# Arduino_connectors.net
KiCad netlist of a schematic drawn in Altium Designer
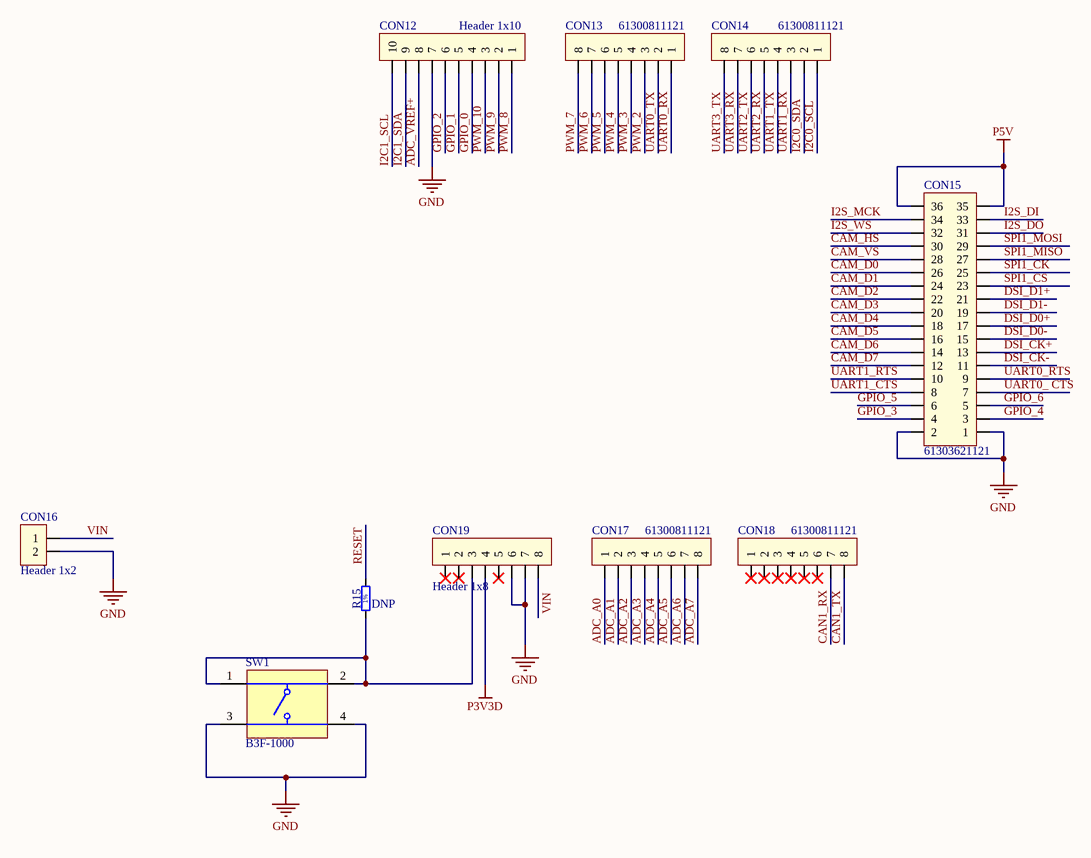
[diagram p0: Arduino connectors.SchDoc]

(export (version "E")
  (design (tool "Eeschema 10.0.6"))
  (components
    (comp (ref "CON12")
      (value "Header 1x10")
      (footprint "61301011121")
      (libsource (lib "MIRION Technologies (CANBERRA Olen) NV") (part "CON10"))
    )
    (comp (ref "CON13")
      (value "61300811121")
      (footprint "61300811121")
      (description "Board-To-Board Connector, Vertical, Wr-Phd Series, Through Hole, Header, 8, 2.54 Mm")
      (libsource (lib "MIRION Technologies (CANBERRA Olen) NV") (part "CON8"))
    )
    (comp (ref "CON14")
      (value "61300811121")
      (footprint "61300811121")
      (description "Board-To-Board Connector, Vertical, Wr-Phd Series, Through Hole, Header, 8, 2.54 Mm")
      (libsource (lib "MIRION Technologies (CANBERRA Olen) NV") (part "CON8"))
    )
    (comp (ref "CON15")
      (value "61303621121")
      (footprint "61303621121")
      (libsource (lib "MIRION Technologies (CANBERRA Olen) NV") (part "CON36"))
    )
    (comp (ref "CON16")
      (value "Header 1x2")
      (footprint "61300211121")
      (description "Header 1x2 2.54mm")
      (libsource (lib "MIRION Technologies (CANBERRA Olen) NV") (part "CON2"))
    )
    (comp (ref "CON17")
      (value "61300811121")
      (footprint "61300811121")
      (description "Board-To-Board Connector, Vertical, Wr-Phd Series, Through Hole, Header, 8, 2.54 Mm")
      (libsource (lib "") (part "CON8_1"))
    )
    (comp (ref "CON18")
      (value "61300811121")
      (footprint "61300811121")
      (description "Board-To-Board Connector, Vertical, Wr-Phd Series, Through Hole, Header, 8, 2.54 Mm")
      (libsource (lib "") (part "CON8_1"))
    )
    (comp (ref "CON19") (value "Header 1x8") (footprint "61300811121") (libsource (lib "") (part "CON8_1")))
    (comp (ref "R15")
      (value "DNP")
      (footprint "R0603")
      (description "generic 0603 Thick film resistor")
      (fields (field (name "VOLTAGE") "75V") (field (name "POWER") "100mW"))
      (libsource (lib "MIRION Technologies (CANBERRA Olen) NV") (part "res_1pct"))
    )
    (comp (ref "SW1")
      (value "B3F-1000")
      (footprint "OMRON-B3F-1000-4_V")
      (description "Tactile Switch, SPST-NO, 0.05 A, 24 V, -25 to 70 degC, 4-Pin THD, RoHS, Bulk")
      (fields (field (name "MANUFACTURER") "Omron Electronic Components"))
      (libsource (lib "MIRION Technologies (CANBERRA Olen) NV") (part "SW-SPST-4_A"))
    )
  )
  (nets
    (net (code "1") (name "/ADC_A0") (class "Default")
      (node (ref "CON17") (pin "1") (pinfunction "1_1") (pintype "passive"))
    )
    (net (code "2") (name "/ADC_A1") (class "Default")
      (node (ref "CON17") (pin "2") (pinfunction "2_2") (pintype "passive"))
    )
    (net (code "3") (name "/ADC_A2") (class "Default")
      (node (ref "CON17") (pin "3") (pinfunction "3_3") (pintype "passive"))
    )
    (net (code "4") (name "/ADC_A3") (class "Default")
      (node (ref "CON17") (pin "4") (pinfunction "4_4") (pintype "passive"))
    )
    (net (code "5") (name "/ADC_A4") (class "Default")
      (node (ref "CON17") (pin "5") (pinfunction "5_5") (pintype "passive"))
    )
    (net (code "6") (name "/ADC_A5") (class "Default")
      (node (ref "CON17") (pin "6") (pinfunction "6_6") (pintype "passive"))
    )
    (net (code "7") (name "/ADC_A6") (class "Default")
      (node (ref "CON17") (pin "7") (pinfunction "7_7") (pintype "passive"))
    )
    (net (code "8") (name "/ADC_A7") (class "Default")
      (node (ref "CON17") (pin "8") (pinfunction "8_8") (pintype "passive"))
    )
    (net (code "9") (name "/ADC_VREF+") (class "Default")
      (node (ref "CON12") (pin "8") (pinfunction "8_8") (pintype "passive"))
    )
    (net (code "10") (name "/CAM_D0") (class "Default")
      (node (ref "CON15") (pin "26") (pinfunction "26_26") (pintype "passive"))
    )
    (net (code "11") (name "/CAM_D1") (class "Default")
      (node (ref "CON15") (pin "24") (pinfunction "24_24") (pintype "passive"))
    )
    (net (code "12") (name "/CAM_D2") (class "Default")
      (node (ref "CON15") (pin "22") (pinfunction "22_22") (pintype "passive"))
    )
    (net (code "13") (name "/CAM_D3") (class "Default")
      (node (ref "CON15") (pin "20") (pinfunction "20_20") (pintype "passive"))
    )
    (net (code "14") (name "/CAM_D4") (class "Default")
      (node (ref "CON15") (pin "18") (pinfunction "18_18") (pintype "passive"))
    )
    (net (code "15") (name "/CAM_D5") (class "Default")
      (node (ref "CON15") (pin "16") (pinfunction "16_16") (pintype "passive"))
    )
    (net (code "16") (name "/CAM_D6") (class "Default")
      (node (ref "CON15") (pin "14") (pinfunction "14_14") (pintype "passive"))
    )
    (net (code "17") (name "/CAM_D7") (class "Default")
      (node (ref "CON15") (pin "12") (pinfunction "12_12") (pintype "passive"))
    )
    (net (code "18") (name "/CAM_HS") (class "Default")
      (node (ref "CON15") (pin "30") (pinfunction "30_30") (pintype "passive"))
    )
    (net (code "19") (name "/CAM_VS") (class "Default")
      (node (ref "CON15") (pin "28") (pinfunction "28_28") (pintype "passive"))
    )
    (net (code "20") (name "/CAN1_RX") (class "Default")
      (node (ref "CON18") (pin "7") (pinfunction "7_7") (pintype "passive"))
    )
    (net (code "21") (name "/CAN1_TX") (class "Default")
      (node (ref "CON18") (pin "8") (pinfunction "8_8") (pintype "passive"))
    )
    (net (code "22") (name "/DSI_CK+") (class "Default")
      (node (ref "CON15") (pin "13") (pinfunction "13_13") (pintype "passive"))
    )
    (net (code "23") (name "/DSI_CK-") (class "Default")
      (node (ref "CON15") (pin "11") (pinfunction "11_11") (pintype "passive"))
    )
    (net (code "24") (name "/DSI_D0+") (class "Default")
      (node (ref "CON15") (pin "17") (pinfunction "17_17") (pintype "passive"))
    )
    (net (code "25") (name "/DSI_D0-") (class "Default")
      (node (ref "CON15") (pin "15") (pinfunction "15_15") (pintype "passive"))
    )
    (net (code "26") (name "/DSI_D1+") (class "Default")
      (node (ref "CON15") (pin "21") (pinfunction "21_21") (pintype "passive"))
    )
    (net (code "27") (name "/DSI_D1-") (class "Default")
      (node (ref "CON15") (pin "19") (pinfunction "19_19") (pintype "passive"))
    )
    (net (code "28") (name "/GPIO_0") (class "Default")
      (node (ref "CON12") (pin "4") (pinfunction "4_4") (pintype "passive"))
    )
    (net (code "29") (name "/GPIO_1") (class "Default")
      (node (ref "CON12") (pin "5") (pinfunction "5_5") (pintype "passive"))
    )
    (net (code "30") (name "/GPIO_2") (class "Default")
      (node (ref "CON12") (pin "6") (pinfunction "6_6") (pintype "passive"))
    )
    (net (code "31") (name "/GPIO_3") (class "Default")
      (node (ref "CON15") (pin "4") (pinfunction "4_4") (pintype "passive"))
    )
    (net (code "32") (name "/GPIO_4") (class "Default")
      (node (ref "CON15") (pin "3") (pinfunction "3_3") (pintype "passive"))
    )
    (net (code "33") (name "/GPIO_5") (class "Default")
      (node (ref "CON15") (pin "6") (pinfunction "6_6") (pintype "passive"))
    )
    (net (code "34") (name "/GPIO_6") (class "Default")
      (node (ref "CON15") (pin "5") (pinfunction "5_5") (pintype "passive"))
    )
    (net (code "35") (name "/I2C0_SCL") (class "Default")
      (node (ref "CON14") (pin "1") (pinfunction "1_1") (pintype "passive"))
    )
    (net (code "36") (name "/I2C0_SDA") (class "Default")
      (node (ref "CON14") (pin "2") (pinfunction "2_2") (pintype "passive"))
    )
    (net (code "37") (name "/I2C1_SCL") (class "Default")
      (node (ref "CON12") (pin "10") (pinfunction "10_10") (pintype "passive"))
    )
    (net (code "38") (name "/I2C1_SDA") (class "Default")
      (node (ref "CON12") (pin "9") (pinfunction "9_9") (pintype "passive"))
    )
    (net (code "39") (name "/I2S_DI") (class "Default")
      (node (ref "CON15") (pin "33") (pinfunction "33_33") (pintype "passive"))
    )
    (net (code "40") (name "/I2S_DO") (class "Default")
      (node (ref "CON15") (pin "31") (pinfunction "31_31") (pintype "passive"))
    )
    (net (code "41") (name "/I2S_MCK") (class "Default")
      (node (ref "CON15") (pin "34") (pinfunction "34_34") (pintype "passive"))
    )
    (net (code "42") (name "/I2S_WS") (class "Default")
      (node (ref "CON15") (pin "32") (pinfunction "32_32") (pintype "passive"))
    )
    (net (code "43") (name "/PWM_2") (class "Default")
      (node (ref "CON13") (pin "3") (pinfunction "3_3") (pintype "passive"))
    )
    (net (code "44") (name "/PWM_3") (class "Default")
      (node (ref "CON13") (pin "4") (pinfunction "4_4") (pintype "passive"))
    )
    (net (code "45") (name "/PWM_4") (class "Default")
      (node (ref "CON13") (pin "5") (pinfunction "5_5") (pintype "passive"))
    )
    (net (code "46") (name "/PWM_5") (class "Default")
      (node (ref "CON13") (pin "6") (pinfunction "6_6") (pintype "passive"))
    )
    (net (code "47") (name "/PWM_6") (class "Default")
      (node (ref "CON13") (pin "7") (pinfunction "7_7") (pintype "passive"))
    )
    (net (code "48") (name "/PWM_7") (class "Default")
      (node (ref "CON13") (pin "8") (pinfunction "8_8") (pintype "passive"))
    )
    (net (code "49") (name "/PWM_8") (class "Default")
      (node (ref "CON12") (pin "1") (pinfunction "1_1") (pintype "passive"))
    )
    (net (code "50") (name "/PWM_9") (class "Default")
      (node (ref "CON12") (pin "2") (pinfunction "2_2") (pintype "passive"))
    )
    (net (code "51") (name "/PWM_10") (class "Default")
      (node (ref "CON12") (pin "3") (pinfunction "3_3") (pintype "passive"))
    )
    (net (code "52") (name "/RESET") (class "Default")
      (node (ref "R15") (pin "2") (pinfunction "2_2") (pintype "passive"))
    )
    (net (code "53") (name "/SPI1_CK") (class "Default")
      (node (ref "CON15") (pin "25") (pinfunction "25_25") (pintype "passive"))
    )
    (net (code "54") (name "/SPI1_CS") (class "Default")
      (node (ref "CON15") (pin "23") (pinfunction "23_23") (pintype "passive"))
    )
    (net (code "55") (name "/SPI1_MISO") (class "Default")
      (node (ref "CON15") (pin "27") (pinfunction "27_27") (pintype "passive"))
    )
    (net (code "56") (name "/SPI1_MOSI") (class "Default")
      (node (ref "CON15") (pin "29") (pinfunction "29_29") (pintype "passive"))
    )
    (net (code "57") (name "/UART0_ CTS") (class "Default")
      (node (ref "CON15") (pin "7") (pinfunction "7_7") (pintype "passive"))
    )
    (net (code "58") (name "/UART0_RTS") (class "Default")
      (node (ref "CON15") (pin "9") (pinfunction "9_9") (pintype "passive"))
    )
    (net (code "59") (name "/UART0_RX") (class "Default")
      (node (ref "CON13") (pin "1") (pinfunction "1_1") (pintype "passive"))
    )
    (net (code "60") (name "/UART0_TX") (class "Default")
      (node (ref "CON13") (pin "2") (pinfunction "2_2") (pintype "passive"))
    )
    (net (code "61") (name "/UART1_CTS") (class "Default")
      (node (ref "CON15") (pin "8") (pinfunction "8_8") (pintype "passive"))
    )
    (net (code "62") (name "/UART1_RTS") (class "Default")
      (node (ref "CON15") (pin "10") (pinfunction "10_10") (pintype "passive"))
    )
    (net (code "63") (name "/UART1_RX") (class "Default")
      (node (ref "CON14") (pin "3") (pinfunction "3_3") (pintype "passive"))
    )
    (net (code "64") (name "/UART1_TX") (class "Default")
      (node (ref "CON14") (pin "4") (pinfunction "4_4") (pintype "passive"))
    )
    (net (code "65") (name "/UART2_RX") (class "Default")
      (node (ref "CON14") (pin "5") (pinfunction "5_5") (pintype "passive"))
    )
    (net (code "66") (name "/UART2_TX") (class "Default")
      (node (ref "CON14") (pin "6") (pinfunction "6_6") (pintype "passive"))
    )
    (net (code "67") (name "/UART3_RX") (class "Default")
      (node (ref "CON14") (pin "7") (pinfunction "7_7") (pintype "passive"))
    )
    (net (code "68") (name "/UART3_TX") (class "Default")
      (node (ref "CON14") (pin "8") (pinfunction "8_8") (pintype "passive"))
    )
    (net (code "69") (name "/VIN") (class "Default")
      (node (ref "CON16") (pin "1") (pinfunction "1_1") (pintype "passive"))
      (node (ref "CON19") (pin "8") (pinfunction "8_8") (pintype "passive"))
    )
    (net (code "70") (name "GND") (class "Default")
      (node (ref "CON12") (pin "7") (pinfunction "7_7") (pintype "passive"))
      (node (ref "CON15") (pin "1") (pinfunction "1_1") (pintype "passive"))
      (node (ref "CON15") (pin "2") (pinfunction "2_2") (pintype "passive"))
      (node (ref "CON16") (pin "2") (pinfunction "2_2") (pintype "passive"))
      (node (ref "CON19") (pin "6") (pinfunction "6_6") (pintype "passive"))
      (node (ref "CON19") (pin "7") (pinfunction "7_7") (pintype "passive"))
      (node (ref "SW1") (pin "3") (pinfunction "3_3") (pintype "passive"))
      (node (ref "SW1") (pin "4") (pinfunction "4_4") (pintype "passive"))
    )
    (net (code "71") (name "Net-(CON19-Pad3)") (class "Default")
      (node (ref "CON19") (pin "3") (pinfunction "3_3") (pintype "passive"))
      (node (ref "R15") (pin "1") (pinfunction "1_1") (pintype "passive"))
      (node (ref "SW1") (pin "1") (pinfunction "1_1") (pintype "passive"))
      (node (ref "SW1") (pin "2") (pinfunction "2_2") (pintype "passive"))
    )
    (net (code "72") (name "P3V3D") (class "Default")
      (node (ref "CON19") (pin "4") (pinfunction "4_4") (pintype "passive"))
    )
    (net (code "73") (name "P5V") (class "Default")
      (node (ref "CON15") (pin "35") (pinfunction "35_35") (pintype "passive"))
      (node (ref "CON15") (pin "36") (pinfunction "36_36") (pintype "passive"))
    )
    (net (code "74") (name "unconnected-(CON18-Pad1)") (class "Default")
      (node (ref "CON18") (pin "1") (pinfunction "1_1") (pintype "passive+no_connect"))
    )
    (net (code "75") (name "unconnected-(CON18-Pad2)") (class "Default")
      (node (ref "CON18") (pin "2") (pinfunction "2_2") (pintype "passive+no_connect"))
    )
    (net (code "76") (name "unconnected-(CON18-Pad3)") (class "Default")
      (node (ref "CON18") (pin "3") (pinfunction "3_3") (pintype "passive+no_connect"))
    )
    (net (code "77") (name "unconnected-(CON18-Pad4)") (class "Default")
      (node (ref "CON18") (pin "4") (pinfunction "4_4") (pintype "passive+no_connect"))
    )
    (net (code "78") (name "unconnected-(CON18-Pad5)") (class "Default")
      (node (ref "CON18") (pin "5") (pinfunction "5_5") (pintype "passive+no_connect"))
    )
    (net (code "79") (name "unconnected-(CON18-Pad6)") (class "Default")
      (node (ref "CON18") (pin "6") (pinfunction "6_6") (pintype "passive+no_connect"))
    )
    (net (code "80") (name "unconnected-(CON19-Pad1)") (class "Default")
      (node (ref "CON19") (pin "1") (pinfunction "1_1") (pintype "passive+no_connect"))
    )
    (net (code "81") (name "unconnected-(CON19-Pad2)") (class "Default")
      (node (ref "CON19") (pin "2") (pinfunction "2_2") (pintype "passive+no_connect"))
    )
    (net (code "82") (name "unconnected-(CON19-Pad5)") (class "Default")
      (node (ref "CON19") (pin "5") (pinfunction "5_5") (pintype "passive+no_connect"))
    )
  )
)
